# Support.net
KiCad netlist of a schematic drawn in Altium Designer
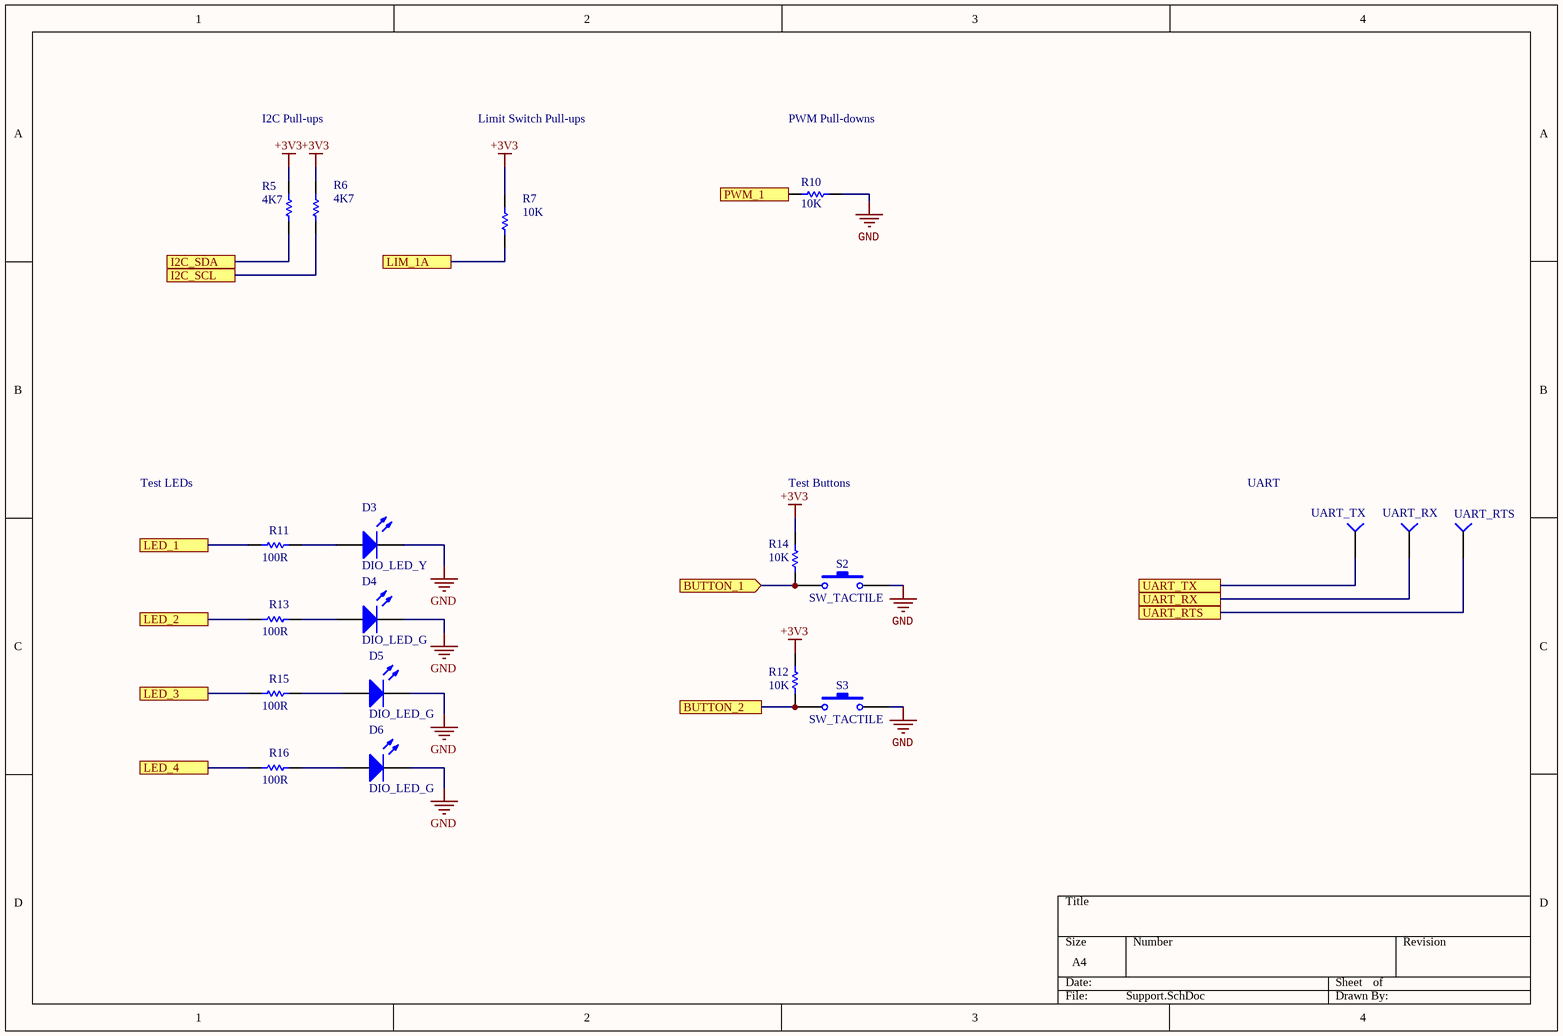
[diagram p0: Support.SchDoc]

(export (version "E")
  (design (tool "Eeschema 10.0.6"))
  (components
    (comp (ref "D3")
      (value "DIO_LED_Y")
      (footprint "LED_0805_LINE")
      (description "LED YELLOW DIFFUSED 0805 SMD")
      (fields (field (name "MANUFACTURER") "OSRAM") (field (name "MPN") "LY R976-PS-36"))
      (libsource (lib "UWRT_Schematic_Library_2020") (part "DIO_LED_Y"))
    )
    (comp (ref "D4")
      (value "DIO_LED_G")
      (footprint "LED_0805_LINE")
      (description "LED GREEN DIFFUSED 0805 SMD")
      (fields (field (name "MANUFACTURER") "OSRAM") (field (name "MPN") "LG R971-KN-1"))
      (libsource (lib "UWRT_Schematic_Library_2020") (part "DIO_LED_G"))
    )
    (comp (ref "D5")
      (value "DIO_LED_G")
      (footprint "LED_0805_LINE")
      (description "LED GREEN DIFFUSED 0805 SMD")
      (fields (field (name "MANUFACTURER") "OSRAM") (field (name "MPN") "LG R971-KN-1"))
      (libsource (lib "UWRT_Schematic_Library_2020") (part "DIO_LED_G"))
    )
    (comp (ref "D6")
      (value "DIO_LED_G")
      (footprint "LED_0805_LINE")
      (description "LED GREEN DIFFUSED 0805 SMD")
      (fields (field (name "MANUFACTURER") "OSRAM") (field (name "MPN") "LG R971-KN-1"))
      (libsource (lib "UWRT_Schematic_Library_2020") (part "DIO_LED_G"))
    )
    (comp (ref "R5")
      (value "4K7")
      (footprint "RESC0603(1608)_N")
      (description "RES SMD 4.7K OHM 5% 1/10W 0603")
      (fields (field (name "MANUFACTURER") "Yageo") (field (name "TOLERANCE") "5%"))
      (libsource (lib "UWRT_Schematic_Library_2020") (part "RES_4K7_0603"))
    )
    (comp (ref "R6")
      (value "4K7")
      (footprint "RESC0603(1608)_N")
      (description "RES SMD 4.7K OHM 5% 1/10W 0603")
      (fields (field (name "MANUFACTURER") "Yageo") (field (name "TOLERANCE") "5%"))
      (libsource (lib "UWRT_Schematic_Library_2020") (part "RES_4K7_0603"))
    )
    (comp (ref "R7")
      (value "10K")
      (footprint "RESC0603(1608)_N")
      (description "RES SMD 10K OHM 5% 1/10W 0603")
      (fields (field (name "MANUFACTURER") "Yageo") (field (name "TOLERANCE") "5%"))
      (libsource (lib "UWRT_Schematic_Library_2020") (part "RES_10K_0603"))
    )
    (comp (ref "R10")
      (value "10K")
      (footprint "RESC0603(1608)_N")
      (description "RES SMD 10K OHM 5% 1/10W 0603")
      (fields (field (name "MANUFACTURER") "Yageo") (field (name "TOLERANCE") "5%"))
      (libsource (lib "UWRT_Schematic_Library_2020") (part "RES_10K_0603"))
    )
    (comp (ref "R11")
      (value "100R")
      (footprint "RESC0603(1608)_N")
      (description "RES SMD 100 OHM 1% 1/10W 0603")
      (fields (field (name "MANUFACTURER") "Yageo") (field (name "TOLERANCE") "1%"))
      (libsource (lib "UWRT_Schematic_Library_2020") (part "RES_100R_0603"))
    )
    (comp (ref "R12")
      (value "10K")
      (footprint "RESC0603(1608)_N")
      (description "RES SMD 10K OHM 5% 1/10W 0603")
      (fields (field (name "MANUFACTURER") "Yageo") (field (name "TOLERANCE") "5%"))
      (libsource (lib "UWRT_Schematic_Library_2020") (part "RES_10K_0603"))
    )
    (comp (ref "R13")
      (value "100R")
      (footprint "RESC0603(1608)_N")
      (description "RES SMD 100 OHM 1% 1/10W 0603")
      (fields (field (name "MANUFACTURER") "Yageo") (field (name "TOLERANCE") "1%"))
      (libsource (lib "UWRT_Schematic_Library_2020") (part "RES_100R_0603"))
    )
    (comp (ref "R14")
      (value "10K")
      (footprint "RESC0603(1608)_N")
      (description "RES SMD 10K OHM 5% 1/10W 0603")
      (fields (field (name "MANUFACTURER") "Yageo") (field (name "TOLERANCE") "5%"))
      (libsource (lib "UWRT_Schematic_Library_2020") (part "RES_10K_0603"))
    )
    (comp (ref "R15")
      (value "100R")
      (footprint "RESC0603(1608)_N")
      (description "RES SMD 100 OHM 1% 1/10W 0603")
      (fields (field (name "MANUFACTURER") "Yageo") (field (name "TOLERANCE") "1%"))
      (libsource (lib "UWRT_Schematic_Library_2020") (part "RES_100R_0603"))
    )
    (comp (ref "R16")
      (value "100R")
      (footprint "RESC0603(1608)_N")
      (description "RES SMD 100 OHM 1% 1/10W 0603")
      (fields (field (name "MANUFACTURER") "Yageo") (field (name "TOLERANCE") "1%"))
      (libsource (lib "UWRT_Schematic_Library_2020") (part "RES_100R_0603"))
    )
    (comp (ref "S2")
      (value "SW_TACTILE")
      (footprint "B3U-1100P")
      (description "Tactile Switch (Grey)")
      (fields (field (name "DIGIKEY PART NUMBER") "SW1021TR-ND") (field (name "MPN") "B3U-1100P"))
      (libsource (lib "UWRT_Schematic_Library_2020") (part "SW_TACTILE"))
    )
    (comp (ref "S3")
      (value "SW_TACTILE")
      (footprint "B3U-1100P")
      (description "Tactile Switch (Grey)")
      (fields (field (name "DIGIKEY PART NUMBER") "SW1021TR-ND") (field (name "MPN") "B3U-1100P"))
      (libsource (lib "UWRT_Schematic_Library_2020") (part "SW_TACTILE"))
    )
    (comp (ref "UART_RTS")
      (value "TESTPOINT")
      (libsource (lib "UWRT_Schematic_Library_2019") (part "TESTPOINT"))
    )
    (comp (ref "UART_RX")
      (value "TESTPOINT")
      (libsource (lib "UWRT_Schematic_Library_2019") (part "TESTPOINT"))
    )
    (comp (ref "UART_TX")
      (value "TESTPOINT")
      (libsource (lib "UWRT_Schematic_Library_2019") (part "TESTPOINT"))
    )
  )
  (nets
    (net (code "1") (name "+3V3") (class "Default")
      (node (ref "R12") (pin "2") (pinfunction "2_2") (pintype "passive"))
      (node (ref "R14") (pin "1") (pinfunction "1_1") (pintype "passive"))
      (node (ref "R5") (pin "2") (pinfunction "2_2") (pintype "passive"))
      (node (ref "R6") (pin "2") (pinfunction "2_2") (pintype "passive"))
      (node (ref "R7") (pin "2") (pinfunction "2_2") (pintype "passive"))
    )
    (net (code "2") (name "/BUTTON_1") (class "Default")
      (node (ref "R14") (pin "2") (pinfunction "2_2") (pintype "passive"))
      (node (ref "S2") (pin "1") (pinfunction "1_1") (pintype "passive"))
    )
    (net (code "3") (name "/BUTTON_2") (class "Default")
      (node (ref "R12") (pin "1") (pinfunction "1_1") (pintype "passive"))
      (node (ref "S3") (pin "1") (pinfunction "1_1") (pintype "passive"))
    )
    (net (code "4") (name "/I2C_SCL") (class "Default")
      (node (ref "R6") (pin "1") (pinfunction "1_1") (pintype "passive"))
    )
    (net (code "5") (name "/I2C_SDA") (class "Default")
      (node (ref "R5") (pin "1") (pinfunction "1_1") (pintype "passive"))
    )
    (net (code "6") (name "/LED_1") (class "Default")
      (node (ref "R11") (pin "1") (pinfunction "1_1") (pintype "passive"))
    )
    (net (code "7") (name "/LED_2") (class "Default")
      (node (ref "R13") (pin "1") (pinfunction "1_1") (pintype "passive"))
    )
    (net (code "8") (name "/LED_3") (class "Default")
      (node (ref "R15") (pin "1") (pinfunction "1_1") (pintype "passive"))
    )
    (net (code "9") (name "/LED_4") (class "Default")
      (node (ref "R16") (pin "1") (pinfunction "1_1") (pintype "passive"))
    )
    (net (code "10") (name "/LIM_1A") (class "Default")
      (node (ref "R7") (pin "1") (pinfunction "1_1") (pintype "passive"))
    )
    (net (code "11") (name "/PWM_1") (class "Default")
      (node (ref "R10") (pin "2") (pinfunction "2_2") (pintype "passive"))
    )
    (net (code "12") (name "/UART_RTS") (class "Default")
      (node (ref "UART_RTS") (pin "1") (pinfunction "=value_1") (pintype "passive"))
    )
    (net (code "13") (name "/UART_RX") (class "Default")
      (node (ref "UART_RX") (pin "1") (pinfunction "=value_1") (pintype "passive"))
    )
    (net (code "14") (name "/UART_TX") (class "Default")
      (node (ref "UART_TX") (pin "1") (pinfunction "=value_1") (pintype "passive"))
    )
    (net (code "15") (name "GND") (class "Default")
      (node (ref "D3") (pin "2") (pinfunction "K_2") (pintype "passive"))
      (node (ref "D4") (pin "2") (pinfunction "K_2") (pintype "passive"))
      (node (ref "D5") (pin "2") (pinfunction "K_2") (pintype "passive"))
      (node (ref "D6") (pin "2") (pinfunction "K_2") (pintype "passive"))
      (node (ref "R10") (pin "1") (pinfunction "1_1") (pintype "passive"))
      (node (ref "S2") (pin "2") (pinfunction "2_2") (pintype "passive"))
      (node (ref "S3") (pin "2") (pinfunction "2_2") (pintype "passive"))
    )
    (net (code "16") (name "Net-(D3-A)") (class "Default")
      (node (ref "D3") (pin "1") (pinfunction "A_1") (pintype "passive"))
      (node (ref "R11") (pin "2") (pinfunction "2_2") (pintype "passive"))
    )
    (net (code "17") (name "Net-(D4-A)") (class "Default")
      (node (ref "D4") (pin "1") (pinfunction "A_1") (pintype "passive"))
      (node (ref "R13") (pin "2") (pinfunction "2_2") (pintype "passive"))
    )
    (net (code "18") (name "Net-(D5-A)") (class "Default")
      (node (ref "D5") (pin "1") (pinfunction "A_1") (pintype "passive"))
      (node (ref "R15") (pin "2") (pinfunction "2_2") (pintype "passive"))
    )
    (net (code "19") (name "Net-(D6-A)") (class "Default")
      (node (ref "D6") (pin "1") (pinfunction "A_1") (pintype "passive"))
      (node (ref "R16") (pin "2") (pinfunction "2_2") (pintype "passive"))
    )
  )
)
